# Translator.net
KiCad netlist of a schematic drawn in EAGLE
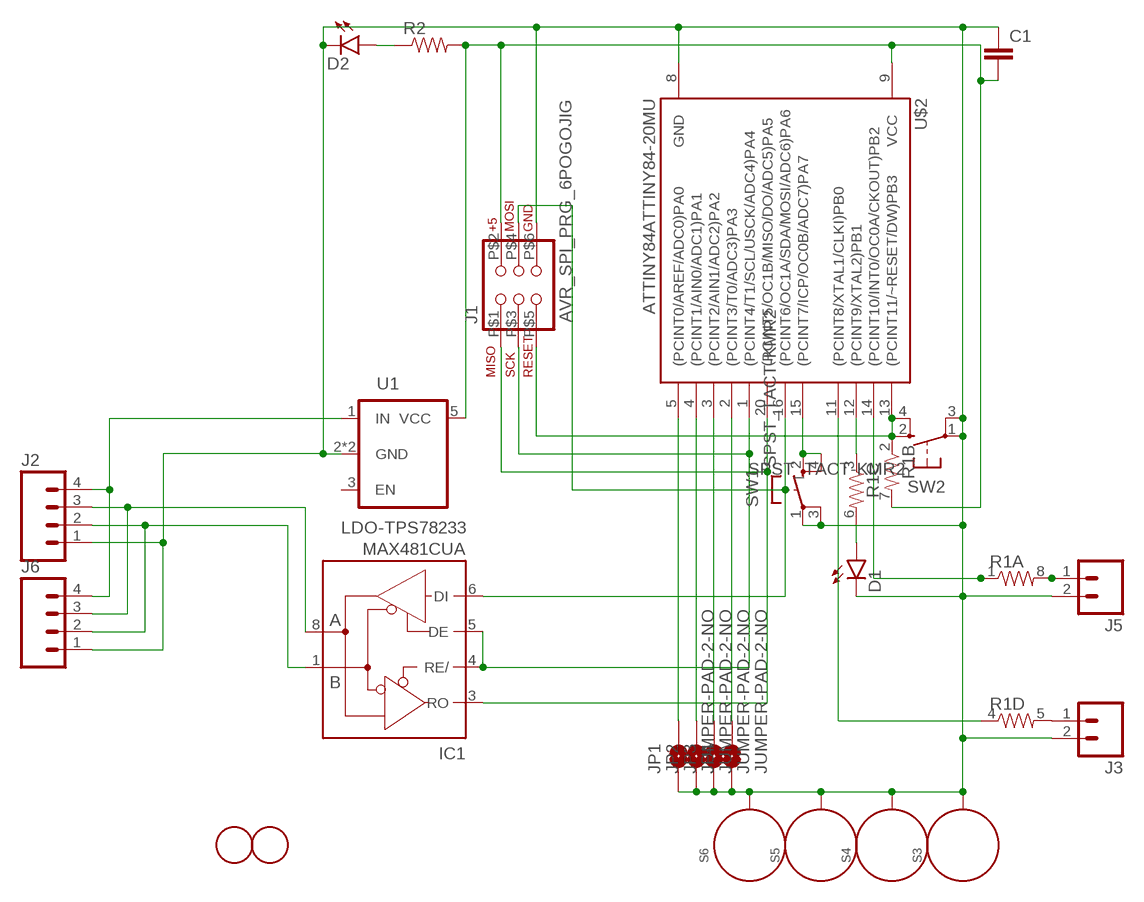
[diagram p0: schematic, sheet 1]

(export (version "E")
  (design (tool "Eeschema 10.0.6"))
  (components
    (comp (ref "C1")
      (value "CAP0805")
      (footprint "eagle-import:0805")
      (libsource (lib "eagle-import") (part "CAP0805"))
    )
    (comp (ref "D1")
      (value "LED1206")
      (footprint "eagle-import:LED-1206")
      (libsource (lib "eagle-import") (part "LED1206"))
    )
    (comp (ref "D2")
      (value "LED1206")
      (footprint "eagle-import:LED-1206")
      (libsource (lib "eagle-import") (part "LED1206"))
    )
    (comp (ref "IC1")
      (value "MAX481CUA")
      (footprint "eagle-import:UMAX8")
      (fields (field (name "MPN") "MAX481CUA+"))
      (libsource (lib "eagle-import") (part "MAX481CUA"))
    )
    (comp (ref "J1")
      (value "AVR_SPI_PRG_6POGOJIG")
      (footprint "eagle-import:2X3_MAX")
      (libsource (lib "eagle-import") (part "AVR_SPI_PRG_6POGOJIG"))
    )
    (comp (ref "J2")
      (value "M04SCREW")
      (footprint "eagle-import:SCREWTERMINAL-3.5MM-4")
      (libsource (lib "eagle-import") (part "M04SCREW"))
    )
    (comp (ref "J3")
      (value "M025MM")
      (footprint "eagle-import:SCREWTERMINAL-5MM-2")
      (libsource (lib "eagle-import") (part "M025MM"))
    )
    (comp (ref "J5")
      (value "M025MM")
      (footprint "eagle-import:SCREWTERMINAL-5MM-2")
      (libsource (lib "eagle-import") (part "M025MM"))
    )
    (comp (ref "J6")
      (value "M04SCREW")
      (footprint "eagle-import:SCREWTERMINAL-3.5MM-4")
      (libsource (lib "eagle-import") (part "M04SCREW"))
    )
    (comp (ref "JP1")
      (value "JUMPER-PAD-2-NO")
      (footprint "eagle-import:PAD-JUMPER-2-NO_NO_SILK")
      (libsource (lib "eagle-import") (part "JUMPER-PAD-2-NO"))
    )
    (comp (ref "JP2")
      (value "JUMPER-PAD-2-NO")
      (footprint "eagle-import:PAD-JUMPER-2-NO_NO_SILK")
      (libsource (lib "eagle-import") (part "JUMPER-PAD-2-NO"))
    )
    (comp (ref "JP3")
      (value "JUMPER-PAD-2-NO")
      (footprint "eagle-import:PAD-JUMPER-2-NO_NO_SILK")
      (libsource (lib "eagle-import") (part "JUMPER-PAD-2-NO"))
    )
    (comp (ref "JP4")
      (value "JUMPER-PAD-2-NO")
      (footprint "eagle-import:PAD-JUMPER-2-NO_NO_SILK")
      (libsource (lib "eagle-import") (part "JUMPER-PAD-2-NO"))
    )
    (comp (ref "R1")
      (value "RESISTOR-ARRAY0603-ARV")
      (footprint "eagle-import:0603-ARV")
      (libsource (lib "eagle-import") (part "RESISTOR-ARRAY0603-ARV"))
    )
    (comp (ref "R2")
      (value "RESISTOR0805-RES")
      (footprint "eagle-import:0805")
      (libsource (lib "eagle-import") (part "RESISTOR0805-RES"))
    )
    (comp (ref "S3")
      (value "STANDOFF_ELECTRICAL")
      (footprint "eagle-import:STANDOFF-ELECTRICAL")
      (libsource (lib "eagle-import") (part "STANDOFF_ELECTRICAL"))
    )
    (comp (ref "S4")
      (value "STANDOFF_ELECTRICAL")
      (footprint "eagle-import:STANDOFF-ELECTRICAL")
      (libsource (lib "eagle-import") (part "STANDOFF_ELECTRICAL"))
    )
    (comp (ref "S5")
      (value "STANDOFF_ELECTRICAL")
      (footprint "eagle-import:STANDOFF-ELECTRICAL")
      (libsource (lib "eagle-import") (part "STANDOFF_ELECTRICAL"))
    )
    (comp (ref "S6")
      (value "STANDOFF_ELECTRICAL")
      (footprint "eagle-import:STANDOFF-ELECTRICAL")
      (libsource (lib "eagle-import") (part "STANDOFF_ELECTRICAL"))
    )
    (comp (ref "SW1")
      (value "SPST_TACT-KMR2")
      (footprint "eagle-import:KMR2")
      (libsource (lib "eagle-import") (part "SPST_TACT-KMR2"))
    )
    (comp (ref "SW2")
      (value "SPST_TACT-KMR2")
      (footprint "eagle-import:KMR2")
      (libsource (lib "eagle-import") (part "SPST_TACT-KMR2"))
    )
    (comp (ref "U$2")
      (value "ATTINY84ATTINY84-20MU")
      (footprint "eagle-import:QFN20")
      (libsource (lib "eagle-import") (part "ATTINY84ATTINY84-20MU"))
    )
    (comp (ref "U$3")
      (value "FIDUCIAL")
      (footprint "eagle-import:FIDUCIAL_1MM")
      (libsource (lib "eagle-import") (part "FIDUCIAL"))
    )
    (comp (ref "U$4")
      (value "FIDUCIAL")
      (footprint "eagle-import:FIDUCIAL_1MM")
      (libsource (lib "eagle-import") (part "FIDUCIAL"))
    )
    (comp (ref "U1")
      (value "LDO-TPS78233")
      (footprint "eagle-import:SOT23-5")
      (libsource (lib "eagle-import") (part "LDO-TPS78233"))
    )
  )
  (nets
    (net (code "1") (name "Net-(D2-PadA)") (class "Default")
      (node (ref "D2") (pin "A") (pinfunction "A_A") (pintype "passive"))
      (node (ref "R2") (pin "1") (pinfunction "1_1") (pintype "passive"))
    )
    (net (code "2") (name "Net-(IC1A-A)") (class "Default")
      (node (ref "IC1") (pin "8") (pinfunction "A_8") (pintype "passive"))
      (node (ref "J2") (pin "3") (pinfunction "3_3") (pintype "passive"))
      (node (ref "J6") (pin "3") (pinfunction "3_3") (pintype "passive"))
    )
    (net (code "3") (name "Net-(IC1A-B)") (class "Default")
      (node (ref "IC1") (pin "1") (pinfunction "B_1") (pintype "passive"))
      (node (ref "J2") (pin "2") (pinfunction "2_2") (pintype "passive"))
      (node (ref "J6") (pin "2") (pinfunction "2_2") (pintype "passive"))
    )
    (net (code "4") (name "Net-(IC1A-DE)") (class "Default")
      (node (ref "IC1") (pin "4") (pinfunction "RE/_4") (pintype "input"))
      (node (ref "IC1") (pin "5") (pinfunction "DE_5") (pintype "input"))
      (node (ref "J1") (pin "P$3") (pinfunction "SCK_P$3") (pintype "passive"))
      (node (ref "U$2") (pin "1") (pinfunction "(PCINT4/T1/SCL/USCK/ADC4)PA4_1") (pintype "bidirectional"))
    )
    (net (code "5") (name "Net-(IC1A-DI)") (class "Default")
      (node (ref "IC1") (pin "6") (pinfunction "DI_6") (pintype "input"))
      (node (ref "J1") (pin "P$4") (pinfunction "MOSI_P$4") (pintype "passive"))
      (node (ref "U$2") (pin "16") (pinfunction "(PCINT6/OC1A/SDA/MOSI/ADC6)PA6_16") (pintype "bidirectional"))
    )
    (net (code "6") (name "Net-(IC1A-RO)") (class "Default")
      (node (ref "IC1") (pin "3") (pinfunction "RO_3") (pintype "output"))
      (node (ref "J1") (pin "P$1") (pinfunction "MISO_P$1") (pintype "passive"))
      (node (ref "U$2") (pin "20") (pinfunction "(PCINT5/OC1B/MISO/DO/ADC5)PA5_20") (pintype "bidirectional"))
    )
    (net (code "7") (name "Net-(J1-GND)") (class "Default")
      (node (ref "C1") (pin "1") (pinfunction "1_1") (pintype "passive"))
      (node (ref "D1") (pin "C") (pinfunction "C_C") (pintype "passive"))
      (node (ref "D2") (pin "C") (pinfunction "C_C") (pintype "passive"))
      (node (ref "J1") (pin "P$6") (pinfunction "GND_P$6") (pintype "passive"))
      (node (ref "J2") (pin "1") (pinfunction "1_1") (pintype "passive"))
      (node (ref "J3") (pin "2") (pinfunction "2_2") (pintype "passive"))
      (node (ref "J5") (pin "2") (pinfunction "2_2") (pintype "passive"))
      (node (ref "J6") (pin "1") (pinfunction "1_1") (pintype "passive"))
      (node (ref "JP1") (pin "1") (pinfunction "1_1") (pintype "passive"))
      (node (ref "JP2") (pin "1") (pinfunction "1_1") (pintype "passive"))
      (node (ref "JP3") (pin "1") (pinfunction "1_1") (pintype "passive"))
      (node (ref "JP4") (pin "1") (pinfunction "1_1") (pintype "passive"))
      (node (ref "S3") (pin "P1") (pinfunction "P$1_P1") (pintype "bidirectional"))
      (node (ref "S4") (pin "P1") (pinfunction "P$1_P1") (pintype "bidirectional"))
      (node (ref "S5") (pin "P1") (pinfunction "P$1_P1") (pintype "bidirectional"))
      (node (ref "S6") (pin "P1") (pinfunction "P$1_P1") (pintype "bidirectional"))
      (node (ref "SW1") (pin "1") (pinfunction "P_1") (pintype "passive"))
      (node (ref "SW1") (pin "3") (pinfunction "P1_3") (pintype "passive"))
      (node (ref "SW2") (pin "1") (pinfunction "P_1") (pintype "passive"))
      (node (ref "SW2") (pin "3") (pinfunction "P1_3") (pintype "passive"))
      (node (ref "U$2") (pin "8") (pinfunction "GND_8") (pintype "bidirectional"))
      (node (ref "U1") (pin "2") (pinfunction "GND_2") (pintype "input"))
      (node (ref "U1") (pin "4") (pinfunction "GND_4") (pintype "input"))
    )
    (net (code "8") (name "Net-(J1-RESET)") (class "Default")
      (node (ref "J1") (pin "P$5") (pinfunction "RESET_P$5") (pintype "passive"))
      (node (ref "R1") (pin "2") (pinfunction "1_2") (pintype "passive"))
      (node (ref "SW2") (pin "2") (pinfunction "S_2") (pintype "passive"))
      (node (ref "SW2") (pin "4") (pinfunction "S1_4") (pintype "passive"))
      (node (ref "U$2") (pin "13") (pinfunction "(PCINT11/~{RESET/DW})PB3_13") (pintype "bidirectional"))
    )
    (net (code "9") (name "Net-(J1-VIN)") (class "Default")
      (node (ref "C1") (pin "2") (pinfunction "2_2") (pintype "passive"))
      (node (ref "J1") (pin "P$2") (pinfunction "VIN_P$2") (pintype "passive"))
      (node (ref "R1") (pin "7") (pinfunction "2_7") (pintype "passive"))
      (node (ref "R2") (pin "2") (pinfunction "2_2") (pintype "passive"))
      (node (ref "U$2") (pin "9") (pinfunction "VCC_9") (pintype "bidirectional"))
      (node (ref "U1") (pin "5") (pinfunction "VCC_5") (pintype "power_in"))
    )
    (net (code "10") (name "Net-(R1A-2)") (class "Default")
      (node (ref "J5") (pin "1") (pinfunction "1_1") (pintype "passive"))
      (node (ref "R1") (pin "8") (pinfunction "2_8") (pintype "passive"))
    )
    (net (code "11") (name "Net-(R1C-1)") (class "Default")
      (node (ref "R1") (pin "3") (pinfunction "1_3") (pintype "passive"))
      (node (ref "U$2") (pin "12") (pinfunction "(PCINT9/XTAL2)PB1_12") (pintype "bidirectional"))
    )
    (net (code "12") (name "Net-(R1C-2)") (class "Default")
      (node (ref "D1") (pin "A") (pinfunction "A_A") (pintype "passive"))
      (node (ref "R1") (pin "6") (pinfunction "2_6") (pintype "passive"))
    )
    (net (code "13") (name "Net-(R1D-1)") (class "Default")
      (node (ref "R1") (pin "4") (pinfunction "1_4") (pintype "passive"))
      (node (ref "U$2") (pin "11") (pinfunction "(PCINT8/XTAL1/CLKI)PB0_11") (pintype "bidirectional"))
    )
    (net (code "14") (name "Net-(R1D-2)") (class "Default")
      (node (ref "J3") (pin "1") (pinfunction "1_1") (pintype "passive"))
      (node (ref "R1") (pin "5") (pinfunction "2_5") (pintype "passive"))
    )
    (net (code "15") (name "Net-(SW1-S)") (class "Default")
      (node (ref "SW1") (pin "2") (pinfunction "S_2") (pintype "passive"))
      (node (ref "SW1") (pin "4") (pinfunction "S1_4") (pintype "passive"))
      (node (ref "U$2") (pin "15") (pinfunction "(PCINT7/ICP/OC0B/ADC7)PA7_15") (pintype "bidirectional"))
    )
    (net (code "16") (name "Net-(U$2-(PCINT0{slash}AREF{slash}ADC0)PA0)") (class "Default")
      (node (ref "JP1") (pin "2") (pinfunction "2_2") (pintype "passive"))
      (node (ref "U$2") (pin "5") (pinfunction "(PCINT0/AREF/ADC0)PA0_5") (pintype "bidirectional"))
    )
    (net (code "17") (name "Net-(U$2-(PCINT1{slash}AIN0{slash}ADC1)PA1)") (class "Default")
      (node (ref "JP2") (pin "2") (pinfunction "2_2") (pintype "passive"))
      (node (ref "U$2") (pin "4") (pinfunction "(PCINT1/AIN0/ADC1)PA1_4") (pintype "bidirectional"))
    )
    (net (code "18") (name "Net-(U$2-(PCINT2{slash}AIN1{slash}ADC2)PA2)") (class "Default")
      (node (ref "JP3") (pin "2") (pinfunction "2_2") (pintype "passive"))
      (node (ref "U$2") (pin "3") (pinfunction "(PCINT2/AIN1/ADC2)PA2_3") (pintype "bidirectional"))
    )
    (net (code "19") (name "Net-(U$2-(PCINT3{slash}T0{slash}ADC3)PA3)") (class "Default")
      (node (ref "JP4") (pin "2") (pinfunction "2_2") (pintype "passive"))
      (node (ref "U$2") (pin "2") (pinfunction "(PCINT3/T0/ADC3)PA3_2") (pintype "bidirectional"))
    )
    (net (code "20") (name "Net-(U$2-(PCINT10{slash}INT0{slash}OC0A{slash}CKOUT)PB2)") (class "Default")
      (node (ref "R1") (pin "1") (pinfunction "1_1") (pintype "passive"))
      (node (ref "U$2") (pin "14") (pinfunction "(PCINT10/INT0/OC0A/CKOUT)PB2_14") (pintype "bidirectional"))
    )
    (net (code "21") (name "Net-(U1-IN)") (class "Default")
      (node (ref "J2") (pin "4") (pinfunction "4_4") (pintype "passive"))
      (node (ref "J6") (pin "4") (pinfunction "4_4") (pintype "passive"))
      (node (ref "U1") (pin "1") (pinfunction "IN_1") (pintype "input"))
    )
    (net (code "22") (name "unconnected-(U1-EN-Pad3)") (class "Default")
      (node (ref "U1") (pin "3") (pinfunction "EN_3") (pintype "input"))
    )
  )
)
